# APP_1_Flash_m.net
KiCad netlist of a schematic drawn in Altium Designer
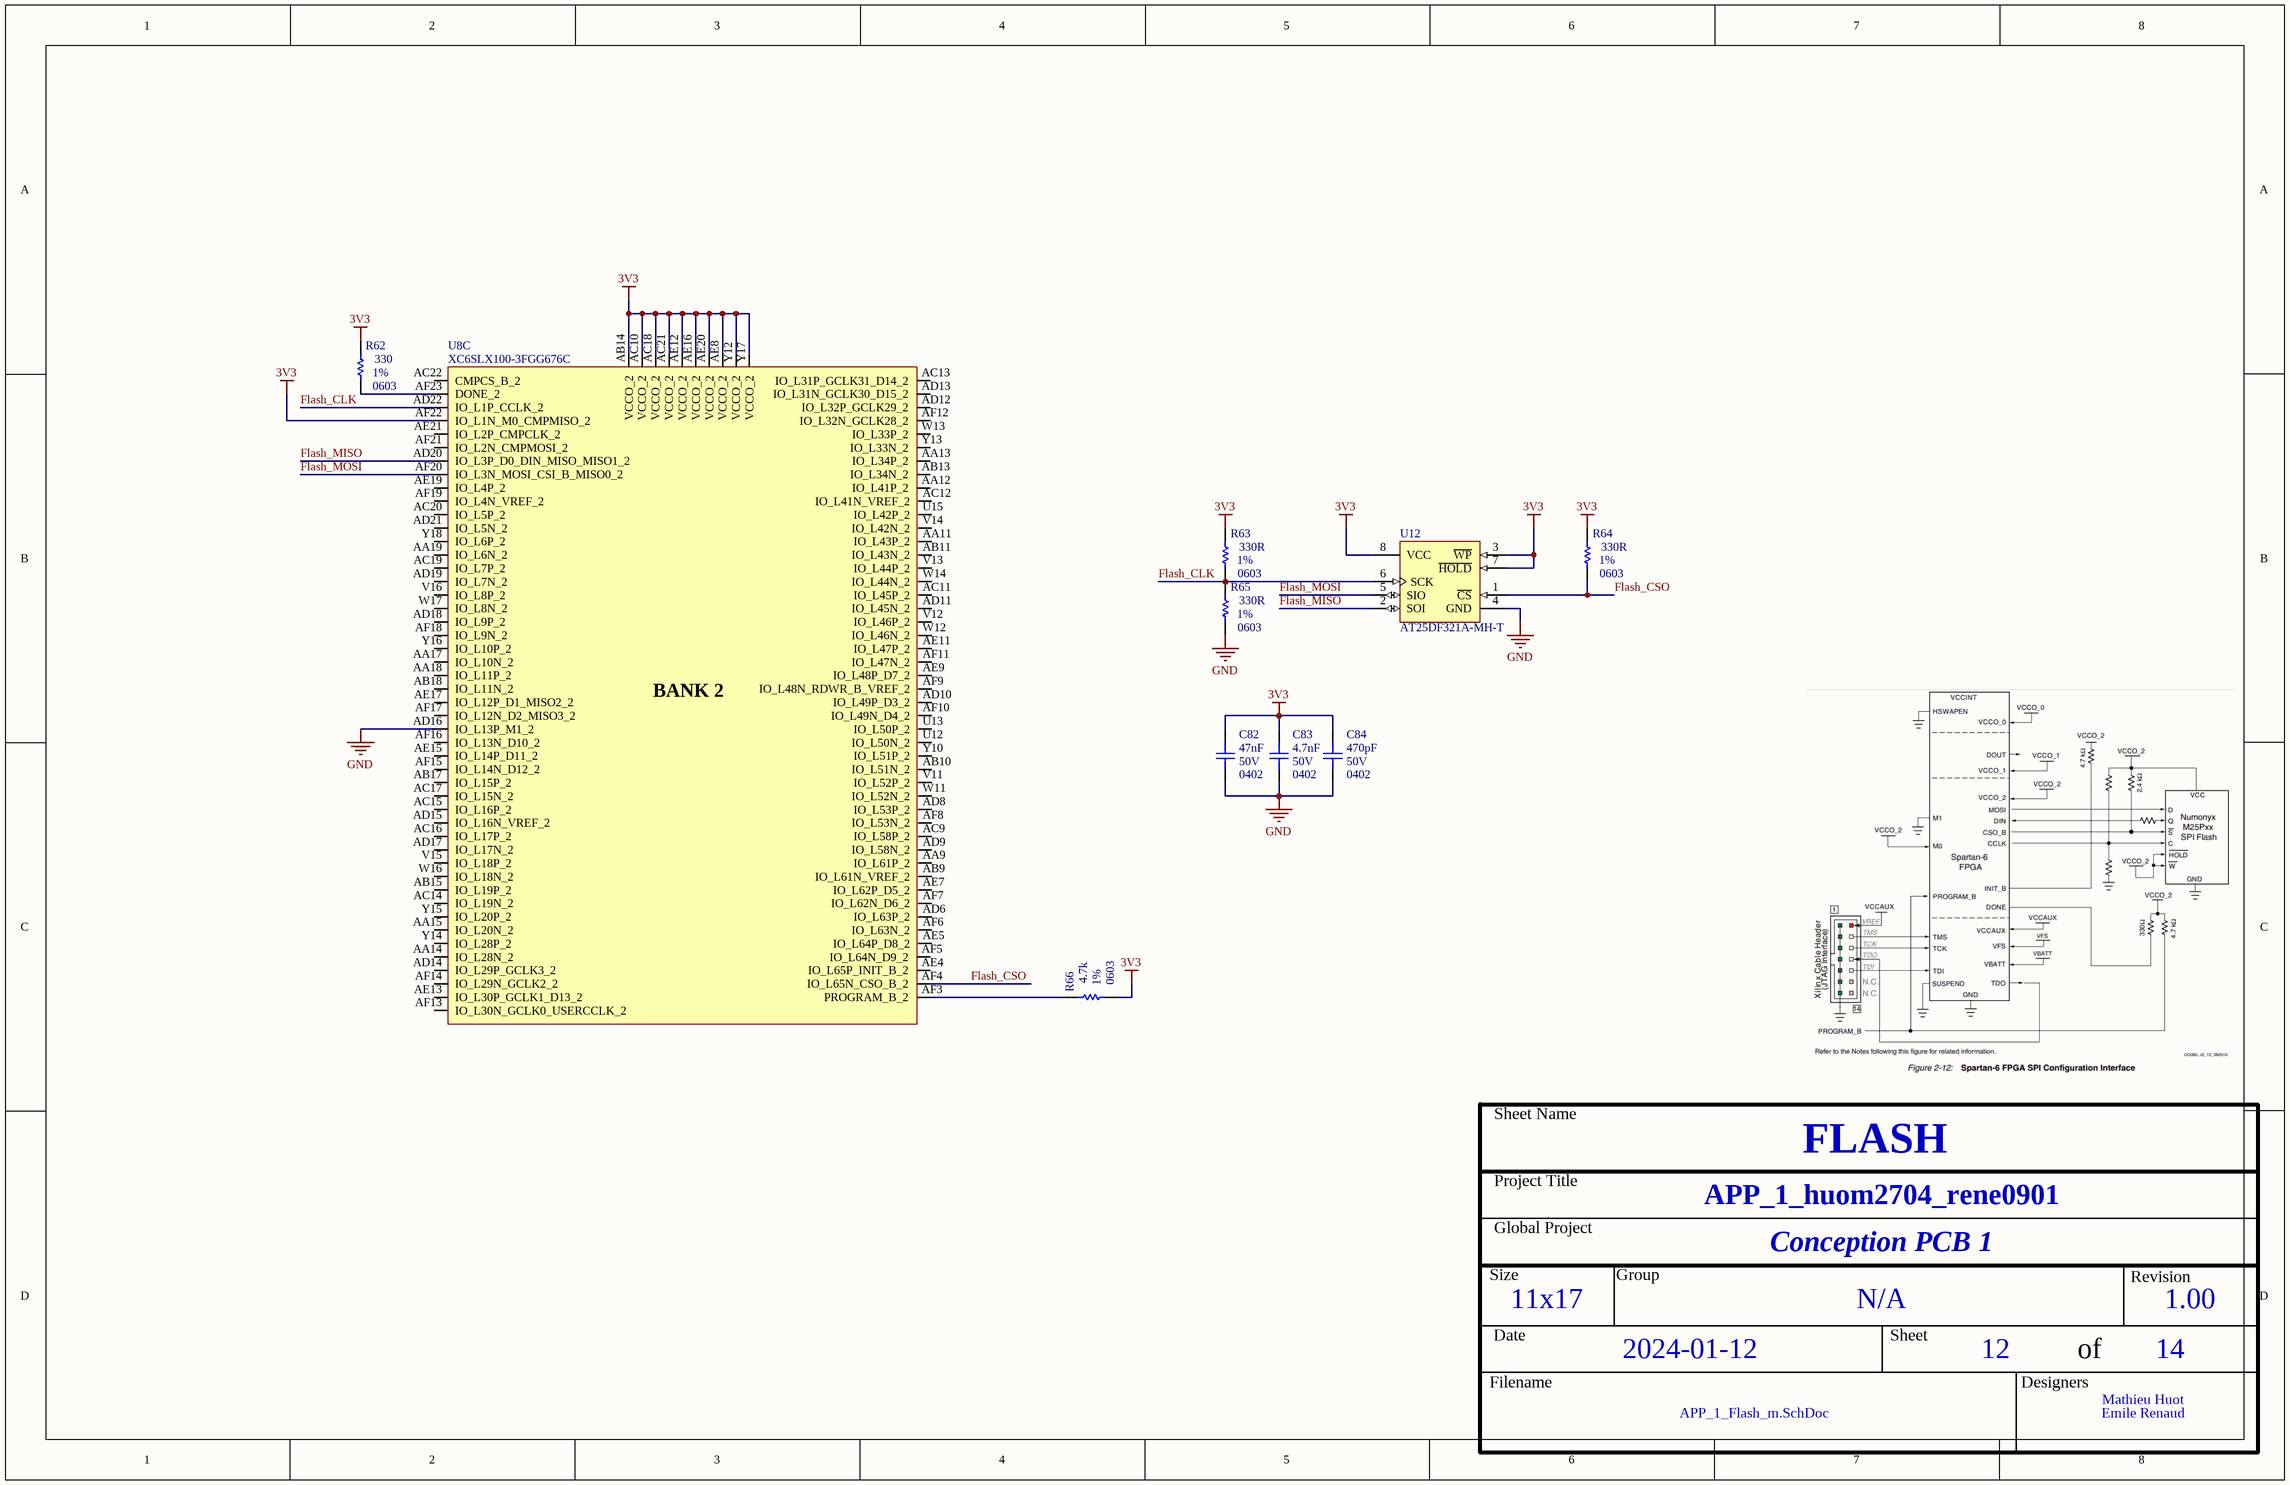
[diagram p0: APP_1_Flash_m.SchDoc]

(export (version "E")
  (design (tool "Eeschema 10.0.6"))
  (components
    (comp (ref "C82")
      (value "47nF")
      (footprint "CAP_0402")
      (description "CAP - 0402")
      (fields
        (field (name "VOLTAGE") "50V")
        (field (name "PACKAGE") "0402")
        (field (name "CREATEDBY") "Jonathan Bouchard")
      )
      (libsource (lib "S7CAS_LIB2023") (part "CAP - 0402"))
    )
    (comp (ref "C83")
      (value "4.7nF")
      (footprint "CAP_0402")
      (description "CAP - 0402")
      (fields
        (field (name "VOLTAGE") "50V")
        (field (name "PACKAGE") "0402")
        (field (name "CREATEDBY") "Jonathan Bouchard")
      )
      (libsource (lib "S7CAS_LIB2023") (part "CAP - 0402"))
    )
    (comp (ref "C84")
      (value "470pF")
      (footprint "CAP_0402")
      (description "CAP - 0402")
      (fields
        (field (name "VOLTAGE") "50V")
        (field (name "PACKAGE") "0402")
        (field (name "CREATEDBY") "Jonathan Bouchard")
      )
      (libsource (lib "S7CAS_LIB2023") (part "CAP - 0402"))
    )
    (comp (ref "R62")
      (value "330")
      (footprint "RES_0603")
      (description "RES - 0603")
      (fields
        (field (name "PACKAGE") "0603")
        (field (name "PRECISION") "1%")
        (field (name "CREATEDBY") "Jonathan Bouchard")
      )
      (libsource (lib "S7CAS_LIB2023") (part "RES - 0603"))
    )
    (comp (ref "R63")
      (value "330R")
      (footprint "RES_0603")
      (description "RES - 0603")
      (fields
        (field (name "PACKAGE") "0603")
        (field (name "PRECISION") "1%")
        (field (name "CREATEDBY") "Jonathan Bouchard")
      )
      (libsource (lib "S7CAS_LIB2023") (part "RES - 0603"))
    )
    (comp (ref "R64")
      (value "330R")
      (footprint "RES_0603")
      (description "RES - 0603")
      (fields
        (field (name "PACKAGE") "0603")
        (field (name "PRECISION") "1%")
        (field (name "CREATEDBY") "Jonathan Bouchard")
      )
      (libsource (lib "S7CAS_LIB2023") (part "RES - 0603"))
    )
    (comp (ref "R65")
      (value "330R")
      (footprint "RES_0603")
      (description "RES - 0603")
      (fields
        (field (name "PACKAGE") "0603")
        (field (name "PRECISION") "1%")
        (field (name "CREATEDBY") "Jonathan Bouchard")
      )
      (libsource (lib "S7CAS_LIB2023") (part "RES - 0603"))
    )
    (comp (ref "R66")
      (value "4.7k")
      (footprint "RES_0603")
      (description "RES - 0603")
      (fields
        (field (name "PACKAGE") "0603")
        (field (name "PRECISION") "1%")
        (field (name "CREATEDBY") "Jonathan Bouchard")
      )
      (libsource (lib "S7CAS_LIB2023") (part "RES - 0603"))
    )
    (comp (ref "U8")
      (value "XC6SLX100-3FGG676C")
      (footprint "FPGA_XILINX_FGG676")
      (description "FPGA - XILINX SPARTAN 6 480 I/O - BGA-676")
      (fields
        (field (name "VOLTAGE") "1.14 V ~ 1.26 V")
        (field (name "MFG") "Xilinx")
        (field (name "CREATEDBY") "Jonathan Bouchard")
      )
      (libsource (lib "S7CAS_LIB2023") (part "FPGA_XC6SLX100-3FGG676C"))
    )
    (comp (ref "U12")
      (value "AT25DF321A-MH-T")
      (footprint "8MA1_UDFN_REN-L")
      (fields (field (name "MANUFACTURER") "Adesto"))
      (libsource (lib "APP_1_Schlib") (part "FLA_AT25DF321A-MH-T"))
    )
  )
  (nets
    (net (code "1") (name "/Flash_CLK") (class "Default")
      (node (ref "R63") (pin "1") (pinfunction "1_1") (pintype "passive"))
      (node (ref "R65") (pin "2") (pinfunction "2_2") (pintype "passive"))
      (node (ref "U12") (pin "6") (pinfunction "SCK_6") (pintype "input"))
      (node (ref "U8") (pin "AD22") (pinfunction "IO_L1P_CCLK_2_AD22") (pintype "passive"))
    )
    (net (code "2") (name "/Flash_CSO") (class "Default")
      (node (ref "R64") (pin "1") (pinfunction "1_1") (pintype "passive"))
      (node (ref "U12") (pin "1") (pinfunction "~{CS}_1") (pintype "input"))
      (node (ref "U8") (pin "AF4") (pinfunction "IO_L65N_CSO_B_2_AF4") (pintype "passive"))
    )
    (net (code "3") (name "/Flash_MISO") (class "Default")
      (node (ref "U12") (pin "2") (pinfunction "SOI_2") (pintype "bidirectional"))
      (node (ref "U8") (pin "AD20") (pinfunction "IO_L3P_D0_DIN_MISO_MISO1_2_AD20") (pintype "passive"))
    )
    (net (code "4") (name "/Flash_MOSI") (class "Default")
      (node (ref "U12") (pin "5") (pinfunction "SIO_5") (pintype "bidirectional"))
      (node (ref "U8") (pin "AF20") (pinfunction "IO_L3N_MOSI_CSI_B_MISO0_2_AF20") (pintype "passive"))
    )
    (net (code "5") (name "3V3") (class "Default")
      (node (ref "C82") (pin "2") (pinfunction "2_2") (pintype "passive"))
      (node (ref "C83") (pin "2") (pinfunction "2_2") (pintype "passive"))
      (node (ref "C84") (pin "2") (pinfunction "2_2") (pintype "passive"))
      (node (ref "R62") (pin "2") (pinfunction "2_2") (pintype "passive"))
      (node (ref "R63") (pin "2") (pinfunction "2_2") (pintype "passive"))
      (node (ref "R64") (pin "2") (pinfunction "2_2") (pintype "passive"))
      (node (ref "R66") (pin "1") (pinfunction "1_1") (pintype "passive"))
      (node (ref "U12") (pin "3") (pinfunction "~{WP}_3") (pintype "input"))
      (node (ref "U12") (pin "7") (pinfunction "~{HOLD}_7") (pintype "input"))
      (node (ref "U12") (pin "8") (pinfunction "VCC_8") (pintype "power_in"))
      (node (ref "U8") (pin "AB14") (pinfunction "VCCO_2_AB14") (pintype "passive"))
      (node (ref "U8") (pin "AC10") (pinfunction "VCCO_2_AC10") (pintype "passive"))
      (node (ref "U8") (pin "AC18") (pinfunction "VCCO_2_AC18") (pintype "passive"))
      (node (ref "U8") (pin "AC21") (pinfunction "VCCO_2_AC21") (pintype "passive"))
      (node (ref "U8") (pin "AE12") (pinfunction "VCCO_2_AE12") (pintype "passive"))
      (node (ref "U8") (pin "AE16") (pinfunction "VCCO_2_AE16") (pintype "passive"))
      (node (ref "U8") (pin "AE20") (pinfunction "VCCO_2_AE20") (pintype "passive"))
      (node (ref "U8") (pin "AE8") (pinfunction "VCCO_2_AE8") (pintype "passive"))
      (node (ref "U8") (pin "AF22") (pinfunction "IO_L1N_M0_CMPMISO_2_AF22") (pintype "passive"))
      (node (ref "U8") (pin "Y12") (pinfunction "VCCO_2_Y12") (pintype "passive"))
      (node (ref "U8") (pin "Y17") (pinfunction "VCCO_2_Y17") (pintype "passive"))
    )
    (net (code "6") (name "GND") (class "Default")
      (node (ref "C82") (pin "1") (pinfunction "1_1") (pintype "passive"))
      (node (ref "C83") (pin "1") (pinfunction "1_1") (pintype "passive"))
      (node (ref "C84") (pin "1") (pinfunction "1_1") (pintype "passive"))
      (node (ref "R65") (pin "1") (pinfunction "1_1") (pintype "passive"))
      (node (ref "U12") (pin "4") (pinfunction "GND_4") (pintype "power_in"))
      (node (ref "U8") (pin "AD16") (pinfunction "IO_L13P_M1_2_AD16") (pintype "passive"))
    )
    (net (code "7") (name "Net-(U8C-DONE_2)") (class "Default")
      (node (ref "R62") (pin "1") (pinfunction "1_1") (pintype "passive"))
      (node (ref "U8") (pin "AF23") (pinfunction "DONE_2_AF23") (pintype "passive"))
    )
    (net (code "8") (name "Net-(U8C-PROGRAM_B_2)") (class "Default")
      (node (ref "R66") (pin "2") (pinfunction "2_2") (pintype "passive"))
      (node (ref "U8") (pin "AF3") (pinfunction "PROGRAM_B_2_AF3") (pintype "passive"))
    )
    (net (code "9") (name "unconnected-(U8C-CMPCS_B_2-PadAC22)") (class "Default")
      (node (ref "U8") (pin "AC22") (pinfunction "CMPCS_B_2_AC22") (pintype "passive"))
    )
    (net (code "10") (name "unconnected-(U8C-IO_L2N_CMPMOSI_2-PadAF21)") (class "Default")
      (node (ref "U8") (pin "AF21") (pinfunction "IO_L2N_CMPMOSI_2_AF21") (pintype "passive"))
    )
    (net (code "11") (name "unconnected-(U8C-IO_L2P_CMPCLK_2-PadAE21)") (class "Default")
      (node (ref "U8") (pin "AE21") (pinfunction "IO_L2P_CMPCLK_2_AE21") (pintype "passive"))
    )
    (net (code "12") (name "unconnected-(U8C-IO_L4N_VREF_2-PadAF19)") (class "Default")
      (node (ref "U8") (pin "AF19") (pinfunction "IO_L4N_VREF_2_AF19") (pintype "passive"))
    )
    (net (code "13") (name "unconnected-(U8C-IO_L4P_2-PadAE19)") (class "Default")
      (node (ref "U8") (pin "AE19") (pinfunction "IO_L4P_2_AE19") (pintype "passive"))
    )
    (net (code "14") (name "unconnected-(U8C-IO_L5N_2-PadAD21)") (class "Default")
      (node (ref "U8") (pin "AD21") (pinfunction "IO_L5N_2_AD21") (pintype "passive"))
    )
    (net (code "15") (name "unconnected-(U8C-IO_L5P_2-PadAC20)") (class "Default")
      (node (ref "U8") (pin "AC20") (pinfunction "IO_L5P_2_AC20") (pintype "passive"))
    )
    (net (code "16") (name "unconnected-(U8C-IO_L6N_2-PadAA19)") (class "Default")
      (node (ref "U8") (pin "AA19") (pinfunction "IO_L6N_2_AA19") (pintype "passive"))
    )
    (net (code "17") (name "unconnected-(U8C-IO_L6P_2-PadY18)") (class "Default")
      (node (ref "U8") (pin "Y18") (pinfunction "IO_L6P_2_Y18") (pintype "passive"))
    )
    (net (code "18") (name "unconnected-(U8C-IO_L7N_2-PadAD19)") (class "Default")
      (node (ref "U8") (pin "AD19") (pinfunction "IO_L7N_2_AD19") (pintype "passive"))
    )
    (net (code "19") (name "unconnected-(U8C-IO_L7P_2-PadAC19)") (class "Default")
      (node (ref "U8") (pin "AC19") (pinfunction "IO_L7P_2_AC19") (pintype "passive"))
    )
    (net (code "20") (name "unconnected-(U8C-IO_L8N_2-PadW17)") (class "Default")
      (node (ref "U8") (pin "W17") (pinfunction "IO_L8N_2_W17") (pintype "passive"))
    )
    (net (code "21") (name "unconnected-(U8C-IO_L8P_2-PadV16)") (class "Default")
      (node (ref "U8") (pin "V16") (pinfunction "IO_L8P_2_V16") (pintype "passive"))
    )
    (net (code "22") (name "unconnected-(U8C-IO_L9N_2-PadAF18)") (class "Default")
      (node (ref "U8") (pin "AF18") (pinfunction "IO_L9N_2_AF18") (pintype "passive"))
    )
    (net (code "23") (name "unconnected-(U8C-IO_L9P_2-PadAD18)") (class "Default")
      (node (ref "U8") (pin "AD18") (pinfunction "IO_L9P_2_AD18") (pintype "passive"))
    )
    (net (code "24") (name "unconnected-(U8C-IO_L10N_2-PadAA17)") (class "Default")
      (node (ref "U8") (pin "AA17") (pinfunction "IO_L10N_2_AA17") (pintype "passive"))
    )
    (net (code "25") (name "unconnected-(U8C-IO_L10P_2-PadY16)") (class "Default")
      (node (ref "U8") (pin "Y16") (pinfunction "IO_L10P_2_Y16") (pintype "passive"))
    )
    (net (code "26") (name "unconnected-(U8C-IO_L11N_2-PadAB18)") (class "Default")
      (node (ref "U8") (pin "AB18") (pinfunction "IO_L11N_2_AB18") (pintype "passive"))
    )
    (net (code "27") (name "unconnected-(U8C-IO_L11P_2-PadAA18)") (class "Default")
      (node (ref "U8") (pin "AA18") (pinfunction "IO_L11P_2_AA18") (pintype "passive"))
    )
    (net (code "28") (name "unconnected-(U8C-IO_L12N_D2_MISO3_2-PadAF17)") (class "Default")
      (node (ref "U8") (pin "AF17") (pinfunction "IO_L12N_D2_MISO3_2_AF17") (pintype "passive"))
    )
    (net (code "29") (name "unconnected-(U8C-IO_L12P_D1_MISO2_2-PadAE17)") (class "Default")
      (node (ref "U8") (pin "AE17") (pinfunction "IO_L12P_D1_MISO2_2_AE17") (pintype "passive"))
    )
    (net (code "30") (name "unconnected-(U8C-IO_L13N_D10_2-PadAF16)") (class "Default")
      (node (ref "U8") (pin "AF16") (pinfunction "IO_L13N_D10_2_AF16") (pintype "passive"))
    )
    (net (code "31") (name "unconnected-(U8C-IO_L14N_D12_2-PadAF15)") (class "Default")
      (node (ref "U8") (pin "AF15") (pinfunction "IO_L14N_D12_2_AF15") (pintype "passive"))
    )
    (net (code "32") (name "unconnected-(U8C-IO_L14P_D11_2-PadAE15)") (class "Default")
      (node (ref "U8") (pin "AE15") (pinfunction "IO_L14P_D11_2_AE15") (pintype "passive"))
    )
    (net (code "33") (name "unconnected-(U8C-IO_L15N_2-PadAC17)") (class "Default")
      (node (ref "U8") (pin "AC17") (pinfunction "IO_L15N_2_AC17") (pintype "passive"))
    )
    (net (code "34") (name "unconnected-(U8C-IO_L15P_2-PadAB17)") (class "Default")
      (node (ref "U8") (pin "AB17") (pinfunction "IO_L15P_2_AB17") (pintype "passive"))
    )
    (net (code "35") (name "unconnected-(U8C-IO_L16N_VREF_2-PadAD15)") (class "Default")
      (node (ref "U8") (pin "AD15") (pinfunction "IO_L16N_VREF_2_AD15") (pintype "passive"))
    )
    (net (code "36") (name "unconnected-(U8C-IO_L16P_2-PadAC15)") (class "Default")
      (node (ref "U8") (pin "AC15") (pinfunction "IO_L16P_2_AC15") (pintype "passive"))
    )
    (net (code "37") (name "unconnected-(U8C-IO_L17N_2-PadAD17)") (class "Default")
      (node (ref "U8") (pin "AD17") (pinfunction "IO_L17N_2_AD17") (pintype "passive"))
    )
    (net (code "38") (name "unconnected-(U8C-IO_L17P_2-PadAC16)") (class "Default")
      (node (ref "U8") (pin "AC16") (pinfunction "IO_L17P_2_AC16") (pintype "passive"))
    )
    (net (code "39") (name "unconnected-(U8C-IO_L18N_2-PadW16)") (class "Default")
      (node (ref "U8") (pin "W16") (pinfunction "IO_L18N_2_W16") (pintype "passive"))
    )
    (net (code "40") (name "unconnected-(U8C-IO_L18P_2-PadV15)") (class "Default")
      (node (ref "U8") (pin "V15") (pinfunction "IO_L18P_2_V15") (pintype "passive"))
    )
    (net (code "41") (name "unconnected-(U8C-IO_L19N_2-PadAC14)") (class "Default")
      (node (ref "U8") (pin "AC14") (pinfunction "IO_L19N_2_AC14") (pintype "passive"))
    )
    (net (code "42") (name "unconnected-(U8C-IO_L19P_2-PadAB15)") (class "Default")
      (node (ref "U8") (pin "AB15") (pinfunction "IO_L19P_2_AB15") (pintype "passive"))
    )
    (net (code "43") (name "unconnected-(U8C-IO_L20N_2-PadAA15)") (class "Default")
      (node (ref "U8") (pin "AA15") (pinfunction "IO_L20N_2_AA15") (pintype "passive"))
    )
    (net (code "44") (name "unconnected-(U8C-IO_L20P_2-PadY15)") (class "Default")
      (node (ref "U8") (pin "Y15") (pinfunction "IO_L20P_2_Y15") (pintype "passive"))
    )
    (net (code "45") (name "unconnected-(U8C-IO_L28N_2-PadAA14)") (class "Default")
      (node (ref "U8") (pin "AA14") (pinfunction "IO_L28N_2_AA14") (pintype "passive"))
    )
    (net (code "46") (name "unconnected-(U8C-IO_L28P_2-PadY14)") (class "Default")
      (node (ref "U8") (pin "Y14") (pinfunction "IO_L28P_2_Y14") (pintype "passive"))
    )
    (net (code "47") (name "unconnected-(U8C-IO_L29N_GCLK2_2-PadAF14)") (class "Default")
      (node (ref "U8") (pin "AF14") (pinfunction "IO_L29N_GCLK2_2_AF14") (pintype "passive"))
    )
    (net (code "48") (name "unconnected-(U8C-IO_L29P_GCLK3_2-PadAD14)") (class "Default")
      (node (ref "U8") (pin "AD14") (pinfunction "IO_L29P_GCLK3_2_AD14") (pintype "passive"))
    )
    (net (code "49") (name "unconnected-(U8C-IO_L30N_GCLK0_USERCCLK_2-PadAF13)") (class "Default")
      (node (ref "U8") (pin "AF13") (pinfunction "IO_L30N_GCLK0_USERCCLK_2_AF13") (pintype "passive"))
    )
    (net (code "50") (name "unconnected-(U8C-IO_L30P_GCLK1_D13_2-PadAE13)") (class "Default")
      (node (ref "U8") (pin "AE13") (pinfunction "IO_L30P_GCLK1_D13_2_AE13") (pintype "passive"))
    )
    (net (code "51") (name "unconnected-(U8C-IO_L31N_GCLK30_D15_2-PadAD13)") (class "Default")
      (node (ref "U8") (pin "AD13") (pinfunction "IO_L31N_GCLK30_D15_2_AD13") (pintype "passive"))
    )
    (net (code "52") (name "unconnected-(U8C-IO_L31P_GCLK31_D14_2-PadAC13)") (class "Default")
      (node (ref "U8") (pin "AC13") (pinfunction "IO_L31P_GCLK31_D14_2_AC13") (pintype "passive"))
    )
    (net (code "53") (name "unconnected-(U8C-IO_L32N_GCLK28_2-PadAF12)") (class "Default")
      (node (ref "U8") (pin "AF12") (pinfunction "IO_L32N_GCLK28_2_AF12") (pintype "passive"))
    )
    (net (code "54") (name "unconnected-(U8C-IO_L32P_GCLK29_2-PadAD12)") (class "Default")
      (node (ref "U8") (pin "AD12") (pinfunction "IO_L32P_GCLK29_2_AD12") (pintype "passive"))
    )
    (net (code "55") (name "unconnected-(U8C-IO_L33N_2-PadY13)") (class "Default")
      (node (ref "U8") (pin "Y13") (pinfunction "IO_L33N_2_Y13") (pintype "passive"))
    )
    (net (code "56") (name "unconnected-(U8C-IO_L33P_2-PadW13)") (class "Default")
      (node (ref "U8") (pin "W13") (pinfunction "IO_L33P_2_W13") (pintype "passive"))
    )
    (net (code "57") (name "unconnected-(U8C-IO_L34N_2-PadAB13)") (class "Default")
      (node (ref "U8") (pin "AB13") (pinfunction "IO_L34N_2_AB13") (pintype "passive"))
    )
    (net (code "58") (name "unconnected-(U8C-IO_L34P_2-PadAA13)") (class "Default")
      (node (ref "U8") (pin "AA13") (pinfunction "IO_L34P_2_AA13") (pintype "passive"))
    )
    (net (code "59") (name "unconnected-(U8C-IO_L41N_VREF_2-PadAC12)") (class "Default")
      (node (ref "U8") (pin "AC12") (pinfunction "IO_L41N_VREF_2_AC12") (pintype "passive"))
    )
    (net (code "60") (name "unconnected-(U8C-IO_L41P_2-PadAA12)") (class "Default")
      (node (ref "U8") (pin "AA12") (pinfunction "IO_L41P_2_AA12") (pintype "passive"))
    )
    (net (code "61") (name "unconnected-(U8C-IO_L42N_2-PadV14)") (class "Default")
      (node (ref "U8") (pin "V14") (pinfunction "IO_L42N_2_V14") (pintype "passive"))
    )
    (net (code "62") (name "unconnected-(U8C-IO_L42P_2-PadU15)") (class "Default")
      (node (ref "U8") (pin "U15") (pinfunction "IO_L42P_2_U15") (pintype "passive"))
    )
    (net (code "63") (name "unconnected-(U8C-IO_L43N_2-PadAB11)") (class "Default")
      (node (ref "U8") (pin "AB11") (pinfunction "IO_L43N_2_AB11") (pintype "passive"))
    )
    (net (code "64") (name "unconnected-(U8C-IO_L43P_2-PadAA11)") (class "Default")
      (node (ref "U8") (pin "AA11") (pinfunction "IO_L43P_2_AA11") (pintype "passive"))
    )
    (net (code "65") (name "unconnected-(U8C-IO_L44N_2-PadW14)") (class "Default")
      (node (ref "U8") (pin "W14") (pinfunction "IO_L44N_2_W14") (pintype "passive"))
    )
    (net (code "66") (name "unconnected-(U8C-IO_L44P_2-PadV13)") (class "Default")
      (node (ref "U8") (pin "V13") (pinfunction "IO_L44P_2_V13") (pintype "passive"))
    )
    (net (code "67") (name "unconnected-(U8C-IO_L45N_2-PadAD11)") (class "Default")
      (node (ref "U8") (pin "AD11") (pinfunction "IO_L45N_2_AD11") (pintype "passive"))
    )
    (net (code "68") (name "unconnected-(U8C-IO_L45P_2-PadAC11)") (class "Default")
      (node (ref "U8") (pin "AC11") (pinfunction "IO_L45P_2_AC11") (pintype "passive"))
    )
    (net (code "69") (name "unconnected-(U8C-IO_L46N_2-PadW12)") (class "Default")
      (node (ref "U8") (pin "W12") (pinfunction "IO_L46N_2_W12") (pintype "passive"))
    )
    (net (code "70") (name "unconnected-(U8C-IO_L46P_2-PadV12)") (class "Default")
      (node (ref "U8") (pin "V12") (pinfunction "IO_L46P_2_V12") (pintype "passive"))
    )
    (net (code "71") (name "unconnected-(U8C-IO_L47N_2-PadAF11)") (class "Default")
      (node (ref "U8") (pin "AF11") (pinfunction "IO_L47N_2_AF11") (pintype "passive"))
    )
    (net (code "72") (name "unconnected-(U8C-IO_L47P_2-PadAE11)") (class "Default")
      (node (ref "U8") (pin "AE11") (pinfunction "IO_L47P_2_AE11") (pintype "passive"))
    )
    (net (code "73") (name "unconnected-(U8C-IO_L48N_RDWR_B_VREF_2-PadAF9)") (class "Default")
      (node (ref "U8") (pin "AF9") (pinfunction "IO_L48N_RDWR_B_VREF_2_AF9") (pintype "passive"))
    )
    (net (code "74") (name "unconnected-(U8C-IO_L48P_D7_2-PadAE9)") (class "Default")
      (node (ref "U8") (pin "AE9") (pinfunction "IO_L48P_D7_2_AE9") (pintype "passive"))
    )
    (net (code "75") (name "unconnected-(U8C-IO_L49N_D4_2-PadAF10)") (class "Default")
      (node (ref "U8") (pin "AF10") (pinfunction "IO_L49N_D4_2_AF10") (pintype "passive"))
    )
    (net (code "76") (name "unconnected-(U8C-IO_L49P_D3_2-PadAD10)") (class "Default")
      (node (ref "U8") (pin "AD10") (pinfunction "IO_L49P_D3_2_AD10") (pintype "passive"))
    )
    (net (code "77") (name "unconnected-(U8C-IO_L50N_2-PadU12)") (class "Default")
      (node (ref "U8") (pin "U12") (pinfunction "IO_L50N_2_U12") (pintype "passive"))
    )
    (net (code "78") (name "unconnected-(U8C-IO_L50P_2-PadU13)") (class "Default")
      (node (ref "U8") (pin "U13") (pinfunction "IO_L50P_2_U13") (pintype "passive"))
    )
    (net (code "79") (name "unconnected-(U8C-IO_L51N_2-PadAB10)") (class "Default")
      (node (ref "U8") (pin "AB10") (pinfunction "IO_L51N_2_AB10") (pintype "passive"))
    )
    (net (code "80") (name "unconnected-(U8C-IO_L51P_2-PadY10)") (class "Default")
      (node (ref "U8") (pin "Y10") (pinfunction "IO_L51P_2_Y10") (pintype "passive"))
    )
    (net (code "81") (name "unconnected-(U8C-IO_L52N_2-PadW11)") (class "Default")
      (node (ref "U8") (pin "W11") (pinfunction "IO_L52N_2_W11") (pintype "passive"))
    )
    (net (code "82") (name "unconnected-(U8C-IO_L52P_2-PadV11)") (class "Default")
      (node (ref "U8") (pin "V11") (pinfunction "IO_L52P_2_V11") (pintype "passive"))
    )
    (net (code "83") (name "unconnected-(U8C-IO_L53N_2-PadAF8)") (class "Default")
      (node (ref "U8") (pin "AF8") (pinfunction "IO_L53N_2_AF8") (pintype "passive"))
    )
    (net (code "84") (name "unconnected-(U8C-IO_L53P_2-PadAD8)") (class "Default")
      (node (ref "U8") (pin "AD8") (pinfunction "IO_L53P_2_AD8") (pintype "passive"))
    )
    (net (code "85") (name "unconnected-(U8C-IO_L58N_2-PadAD9)") (class "Default")
      (node (ref "U8") (pin "AD9") (pinfunction "IO_L58N_2_AD9") (pintype "passive"))
    )
    (net (code "86") (name "unconnected-(U8C-IO_L58P_2-PadAC9)") (class "Default")
      (node (ref "U8") (pin "AC9") (pinfunction "IO_L58P_2_AC9") (pintype "passive"))
    )
    (net (code "87") (name "unconnected-(U8C-IO_L61N_VREF_2-PadAB9)") (class "Default")
      (node (ref "U8") (pin "AB9") (pinfunction "IO_L61N_VREF_2_AB9") (pintype "passive"))
    )
    (net (code "88") (name "unconnected-(U8C-IO_L61P_2-PadAA9)") (class "Default")
      (node (ref "U8") (pin "AA9") (pinfunction "IO_L61P_2_AA9") (pintype "passive"))
    )
    (net (code "89") (name "unconnected-(U8C-IO_L62N_D6_2-PadAF7)") (class "Default")
      (node (ref "U8") (pin "AF7") (pinfunction "IO_L62N_D6_2_AF7") (pintype "passive"))
    )
    (net (code "90") (name "unconnected-(U8C-IO_L62P_D5_2-PadAE7)") (class "Default")
      (node (ref "U8") (pin "AE7") (pinfunction "IO_L62P_D5_2_AE7") (pintype "passive"))
    )
    (net (code "91") (name "unconnected-(U8C-IO_L63N_2-PadAF6)") (class "Default")
      (node (ref "U8") (pin "AF6") (pinfunction "IO_L63N_2_AF6") (pintype "passive"))
    )
    (net (code "92") (name "unconnected-(U8C-IO_L63P_2-PadAD6)") (class "Default")
      (node (ref "U8") (pin "AD6") (pinfunction "IO_L63P_2_AD6") (pintype "passive"))
    )
    (net (code "93") (name "unconnected-(U8C-IO_L64N_D9_2-PadAF5)") (class "Default")
      (node (ref "U8") (pin "AF5") (pinfunction "IO_L64N_D9_2_AF5") (pintype "passive"))
    )
    (net (code "94") (name "unconnected-(U8C-IO_L64P_D8_2-PadAE5)") (class "Default")
      (node (ref "U8") (pin "AE5") (pinfunction "IO_L64P_D8_2_AE5") (pintype "passive"))
    )
    (net (code "95") (name "unconnected-(U8C-IO_L65P_INIT_B_2-PadAE4)") (class "Default")
      (node (ref "U8") (pin "AE4") (pinfunction "IO_L65P_INIT_B_2_AE4") (pintype "passive"))
    )
  )
)
